# CPU_-_Control.net
KiCad netlist of a schematic drawn in Altium Designer
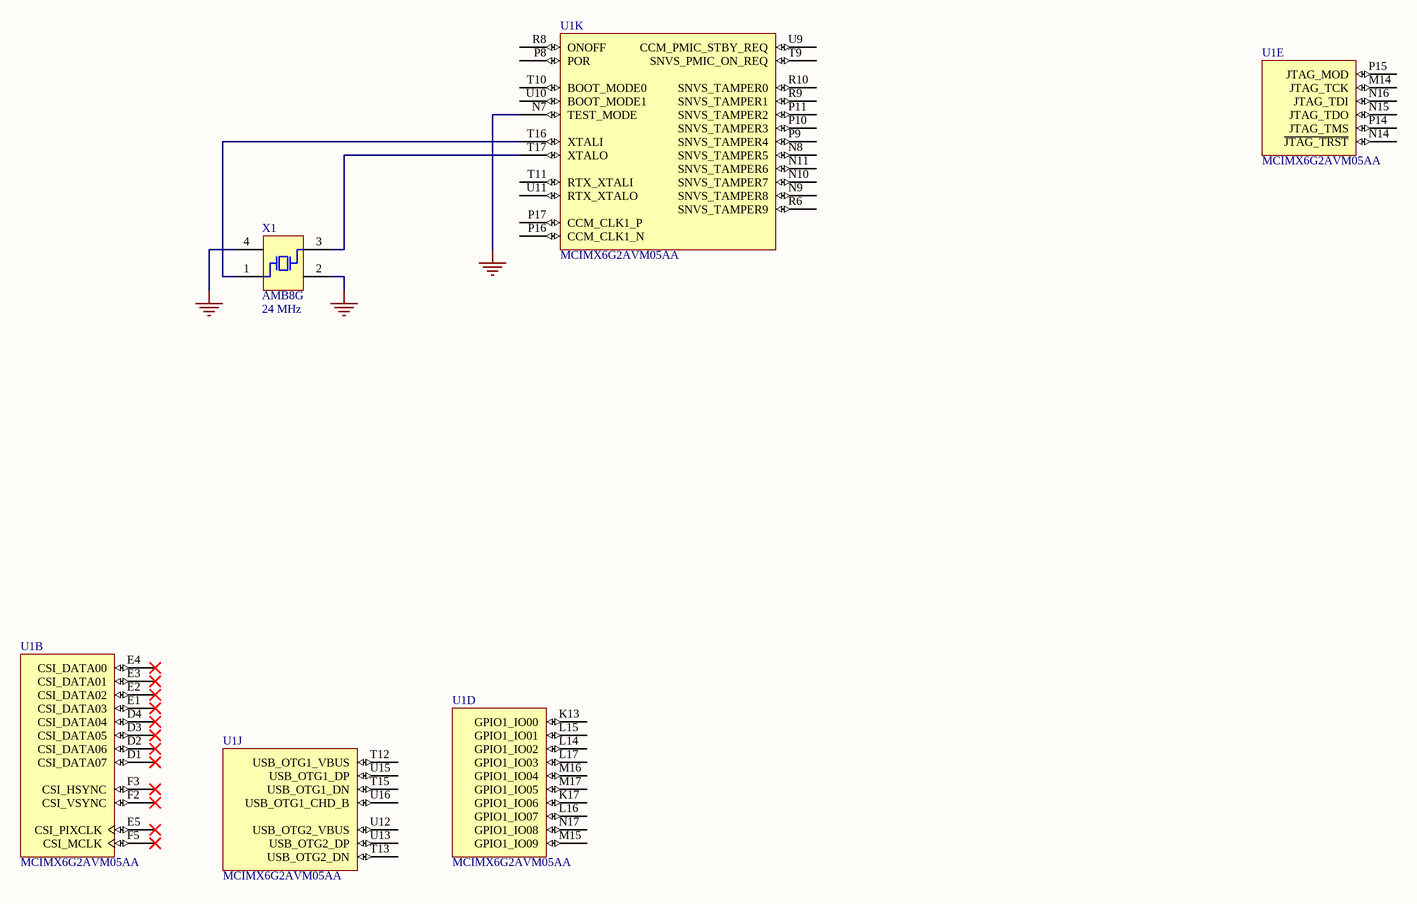
[diagram p0: CPU - Control.SchDoc]

(export (version "E")
  (design (tool "Eeschema 10.0.6"))
  (components
    (comp (ref "U1")
      (value "MCIMX6G2AVM05AA")
      (footprint "BGA289C80P17X17_1400X1400X132")
      (libsource (lib "Hub-UV17") (part "MCIMX6G2AVM05AA"))
    )
    (comp (ref "X1")
      (value "AMB8G")
      (footprint "DFN220P320X100-4N")
      (fields (field (name "ALTIUM_VALUE") "24 MHz"))
      (libsource (lib "Hub-UV17") (part "ABM8G-24.000MHZ-18-D2Y-T"))
    )
  )
  (nets
    (net (code "1") (name "GND") (class "Default")
      (node (ref "U1") (pin "N7") (pinfunction "TEST_MODE_N7") (pintype "bidirectional"))
      (node (ref "X1") (pin "2") (pinfunction "2_2") (pintype "passive"))
      (node (ref "X1") (pin "4") (pinfunction "4_4") (pintype "passive"))
    )
    (net (code "2") (name "Net-(U1K-XTALI)") (class "Default")
      (node (ref "U1") (pin "T16") (pinfunction "XTALI_T16") (pintype "bidirectional"))
      (node (ref "X1") (pin "1") (pinfunction "1_1") (pintype "passive"))
    )
    (net (code "3") (name "Net-(U1K-XTALO)") (class "Default")
      (node (ref "U1") (pin "T17") (pinfunction "XTALO_T17") (pintype "bidirectional"))
      (node (ref "X1") (pin "3") (pinfunction "3_3") (pintype "passive"))
    )
    (net (code "4") (name "unconnected-(U1B-CSI_DATA00-PadE4)") (class "Default")
      (node (ref "U1") (pin "E4") (pinfunction "CSI_DATA00_E4") (pintype "bidirectional+no_connect"))
    )
    (net (code "5") (name "unconnected-(U1B-CSI_DATA01-PadE3)") (class "Default")
      (node (ref "U1") (pin "E3") (pinfunction "CSI_DATA01_E3") (pintype "bidirectional+no_connect"))
    )
    (net (code "6") (name "unconnected-(U1B-CSI_DATA02-PadE2)") (class "Default")
      (node (ref "U1") (pin "E2") (pinfunction "CSI_DATA02_E2") (pintype "bidirectional+no_connect"))
    )
    (net (code "7") (name "unconnected-(U1B-CSI_DATA03-PadE1)") (class "Default")
      (node (ref "U1") (pin "E1") (pinfunction "CSI_DATA03_E1") (pintype "bidirectional+no_connect"))
    )
    (net (code "8") (name "unconnected-(U1B-CSI_DATA04-PadD4)") (class "Default")
      (node (ref "U1") (pin "D4") (pinfunction "CSI_DATA04_D4") (pintype "bidirectional+no_connect"))
    )
    (net (code "9") (name "unconnected-(U1B-CSI_DATA05-PadD3)") (class "Default")
      (node (ref "U1") (pin "D3") (pinfunction "CSI_DATA05_D3") (pintype "bidirectional+no_connect"))
    )
    (net (code "10") (name "unconnected-(U1B-CSI_DATA06-PadD2)") (class "Default")
      (node (ref "U1") (pin "D2") (pinfunction "CSI_DATA06_D2") (pintype "bidirectional+no_connect"))
    )
    (net (code "11") (name "unconnected-(U1B-CSI_DATA07-PadD1)") (class "Default")
      (node (ref "U1") (pin "D1") (pinfunction "CSI_DATA07_D1") (pintype "bidirectional+no_connect"))
    )
    (net (code "12") (name "unconnected-(U1B-CSI_HSYNC-PadF3)") (class "Default")
      (node (ref "U1") (pin "F3") (pinfunction "CSI_HSYNC_F3") (pintype "bidirectional+no_connect"))
    )
    (net (code "13") (name "unconnected-(U1B-CSI_MCLK-PadF5)") (class "Default")
      (node (ref "U1") (pin "F5") (pinfunction "CSI_MCLK_F5") (pintype "bidirectional+no_connect"))
    )
    (net (code "14") (name "unconnected-(U1B-CSI_PIXCLK-PadE5)") (class "Default")
      (node (ref "U1") (pin "E5") (pinfunction "CSI_PIXCLK_E5") (pintype "bidirectional+no_connect"))
    )
    (net (code "15") (name "unconnected-(U1B-CSI_VSYNC-PadF2)") (class "Default")
      (node (ref "U1") (pin "F2") (pinfunction "CSI_VSYNC_F2") (pintype "bidirectional+no_connect"))
    )
    (net (code "16") (name "unconnected-(U1D-GPIO1_IO00-PadK13)") (class "Default")
      (node (ref "U1") (pin "K13") (pinfunction "GPIO1_IO00_K13") (pintype "bidirectional"))
    )
    (net (code "17") (name "unconnected-(U1D-GPIO1_IO01-PadL15)") (class "Default")
      (node (ref "U1") (pin "L15") (pinfunction "GPIO1_IO01_L15") (pintype "bidirectional"))
    )
    (net (code "18") (name "unconnected-(U1D-GPIO1_IO02-PadL14)") (class "Default")
      (node (ref "U1") (pin "L14") (pinfunction "GPIO1_IO02_L14") (pintype "bidirectional"))
    )
    (net (code "19") (name "unconnected-(U1D-GPIO1_IO03-PadL17)") (class "Default")
      (node (ref "U1") (pin "L17") (pinfunction "GPIO1_IO03_L17") (pintype "bidirectional"))
    )
    (net (code "20") (name "unconnected-(U1D-GPIO1_IO04-PadM16)") (class "Default")
      (node (ref "U1") (pin "M16") (pinfunction "GPIO1_IO04_M16") (pintype "bidirectional"))
    )
    (net (code "21") (name "unconnected-(U1D-GPIO1_IO05-PadM17)") (class "Default")
      (node (ref "U1") (pin "M17") (pinfunction "GPIO1_IO05_M17") (pintype "bidirectional"))
    )
    (net (code "22") (name "unconnected-(U1D-GPIO1_IO06-PadK17)") (class "Default")
      (node (ref "U1") (pin "K17") (pinfunction "GPIO1_IO06_K17") (pintype "bidirectional"))
    )
    (net (code "23") (name "unconnected-(U1D-GPIO1_IO07-PadL16)") (class "Default")
      (node (ref "U1") (pin "L16") (pinfunction "GPIO1_IO07_L16") (pintype "bidirectional"))
    )
    (net (code "24") (name "unconnected-(U1D-GPIO1_IO08-PadN17)") (class "Default")
      (node (ref "U1") (pin "N17") (pinfunction "GPIO1_IO08_N17") (pintype "bidirectional"))
    )
    (net (code "25") (name "unconnected-(U1D-GPIO1_IO09-PadM15)") (class "Default")
      (node (ref "U1") (pin "M15") (pinfunction "GPIO1_IO09_M15") (pintype "bidirectional"))
    )
    (net (code "26") (name "unconnected-(U1E-JTAG_MOD-PadP15)") (class "Default")
      (node (ref "U1") (pin "P15") (pinfunction "JTAG_MOD_P15") (pintype "bidirectional"))
    )
    (net (code "27") (name "unconnected-(U1E-JTAG_TCK-PadM14)") (class "Default")
      (node (ref "U1") (pin "M14") (pinfunction "JTAG_TCK_M14") (pintype "bidirectional"))
    )
    (net (code "28") (name "unconnected-(U1E-JTAG_TDI-PadN16)") (class "Default")
      (node (ref "U1") (pin "N16") (pinfunction "JTAG_TDI_N16") (pintype "bidirectional"))
    )
    (net (code "29") (name "unconnected-(U1E-JTAG_TDO-PadN15)") (class "Default")
      (node (ref "U1") (pin "N15") (pinfunction "JTAG_TDO_N15") (pintype "bidirectional"))
    )
    (net (code "30") (name "unconnected-(U1E-JTAG_TMS-PadP14)") (class "Default")
      (node (ref "U1") (pin "P14") (pinfunction "JTAG_TMS_P14") (pintype "bidirectional"))
    )
    (net (code "31") (name "unconnected-(U1E-~{JTAG_TRST}-PadN14)") (class "Default")
      (node (ref "U1") (pin "N14") (pinfunction "~{JTAG_TRST}_N14") (pintype "bidirectional"))
    )
    (net (code "32") (name "unconnected-(U1J-USB_OTG1_CHD_B-PadU16)") (class "Default")
      (node (ref "U1") (pin "U16") (pinfunction "USB_OTG1_CHD_B_U16") (pintype "bidirectional"))
    )
    (net (code "33") (name "unconnected-(U1J-USB_OTG1_DN-PadT15)") (class "Default")
      (node (ref "U1") (pin "T15") (pinfunction "USB_OTG1_DN_T15") (pintype "bidirectional"))
    )
    (net (code "34") (name "unconnected-(U1J-USB_OTG1_DP-PadU15)") (class "Default")
      (node (ref "U1") (pin "U15") (pinfunction "USB_OTG1_DP_U15") (pintype "bidirectional"))
    )
    (net (code "35") (name "unconnected-(U1J-USB_OTG1_VBUS-PadT12)") (class "Default")
      (node (ref "U1") (pin "T12") (pinfunction "USB_OTG1_VBUS_T12") (pintype "bidirectional"))
    )
    (net (code "36") (name "unconnected-(U1J-USB_OTG2_DN-PadT13)") (class "Default")
      (node (ref "U1") (pin "T13") (pinfunction "USB_OTG2_DN_T13") (pintype "bidirectional"))
    )
    (net (code "37") (name "unconnected-(U1J-USB_OTG2_DP-PadU13)") (class "Default")
      (node (ref "U1") (pin "U13") (pinfunction "USB_OTG2_DP_U13") (pintype "bidirectional"))
    )
    (net (code "38") (name "unconnected-(U1J-USB_OTG2_VBUS-PadU12)") (class "Default")
      (node (ref "U1") (pin "U12") (pinfunction "USB_OTG2_VBUS_U12") (pintype "bidirectional"))
    )
    (net (code "39") (name "unconnected-(U1K-BOOT_MODE0-PadT10)") (class "Default")
      (node (ref "U1") (pin "T10") (pinfunction "BOOT_MODE0_T10") (pintype "bidirectional"))
    )
    (net (code "40") (name "unconnected-(U1K-BOOT_MODE1-PadU10)") (class "Default")
      (node (ref "U1") (pin "U10") (pinfunction "BOOT_MODE1_U10") (pintype "bidirectional"))
    )
    (net (code "41") (name "unconnected-(U1K-CCM_CLK1_N-PadP16)") (class "Default")
      (node (ref "U1") (pin "P16") (pinfunction "CCM_CLK1_N_P16") (pintype "bidirectional"))
    )
    (net (code "42") (name "unconnected-(U1K-CCM_CLK1_P-PadP17)") (class "Default")
      (node (ref "U1") (pin "P17") (pinfunction "CCM_CLK1_P_P17") (pintype "bidirectional"))
    )
    (net (code "43") (name "unconnected-(U1K-CCM_PMIC_STBY_REQ-PadU9)") (class "Default")
      (node (ref "U1") (pin "U9") (pinfunction "CCM_PMIC_STBY_REQ_U9") (pintype "bidirectional"))
    )
    (net (code "44") (name "unconnected-(U1K-ONOFF-PadR8)") (class "Default")
      (node (ref "U1") (pin "R8") (pinfunction "ONOFF_R8") (pintype "bidirectional"))
    )
    (net (code "45") (name "unconnected-(U1K-POR-PadP8)") (class "Default")
      (node (ref "U1") (pin "P8") (pinfunction "POR_P8") (pintype "bidirectional"))
    )
    (net (code "46") (name "unconnected-(U1K-RTX_XTALI-PadT11)") (class "Default")
      (node (ref "U1") (pin "T11") (pinfunction "RTX_XTALI_T11") (pintype "bidirectional"))
    )
    (net (code "47") (name "unconnected-(U1K-RTX_XTALO-PadU11)") (class "Default")
      (node (ref "U1") (pin "U11") (pinfunction "RTX_XTALO_U11") (pintype "bidirectional"))
    )
    (net (code "48") (name "unconnected-(U1K-SNVS_PMIC_ON_REQ-PadT9)") (class "Default")
      (node (ref "U1") (pin "T9") (pinfunction "SNVS_PMIC_ON_REQ_T9") (pintype "bidirectional"))
    )
    (net (code "49") (name "unconnected-(U1K-SNVS_TAMPER0-PadR10)") (class "Default")
      (node (ref "U1") (pin "R10") (pinfunction "SNVS_TAMPER0_R10") (pintype "bidirectional"))
    )
    (net (code "50") (name "unconnected-(U1K-SNVS_TAMPER1-PadR9)") (class "Default")
      (node (ref "U1") (pin "R9") (pinfunction "SNVS_TAMPER1_R9") (pintype "bidirectional"))
    )
    (net (code "51") (name "unconnected-(U1K-SNVS_TAMPER2-PadP11)") (class "Default")
      (node (ref "U1") (pin "P11") (pinfunction "SNVS_TAMPER2_P11") (pintype "bidirectional"))
    )
    (net (code "52") (name "unconnected-(U1K-SNVS_TAMPER3-PadP10)") (class "Default")
      (node (ref "U1") (pin "P10") (pinfunction "SNVS_TAMPER3_P10") (pintype "bidirectional"))
    )
    (net (code "53") (name "unconnected-(U1K-SNVS_TAMPER4-PadP9)") (class "Default")
      (node (ref "U1") (pin "P9") (pinfunction "SNVS_TAMPER4_P9") (pintype "bidirectional"))
    )
    (net (code "54") (name "unconnected-(U1K-SNVS_TAMPER5-PadN8)") (class "Default")
      (node (ref "U1") (pin "N8") (pinfunction "SNVS_TAMPER5_N8") (pintype "bidirectional"))
    )
    (net (code "55") (name "unconnected-(U1K-SNVS_TAMPER6-PadN11)") (class "Default")
      (node (ref "U1") (pin "N11") (pinfunction "SNVS_TAMPER6_N11") (pintype "bidirectional"))
    )
    (net (code "56") (name "unconnected-(U1K-SNVS_TAMPER7-PadN10)") (class "Default")
      (node (ref "U1") (pin "N10") (pinfunction "SNVS_TAMPER7_N10") (pintype "bidirectional"))
    )
    (net (code "57") (name "unconnected-(U1K-SNVS_TAMPER8-PadN9)") (class "Default")
      (node (ref "U1") (pin "N9") (pinfunction "SNVS_TAMPER8_N9") (pintype "bidirectional"))
    )
    (net (code "58") (name "unconnected-(U1K-SNVS_TAMPER9-PadR6)") (class "Default")
      (node (ref "U1") (pin "R6") (pinfunction "SNVS_TAMPER9_R6") (pintype "bidirectional"))
    )
  )
)
